# 03_CONNECTOR.net
KiCad netlist of a schematic drawn in Altium Designer
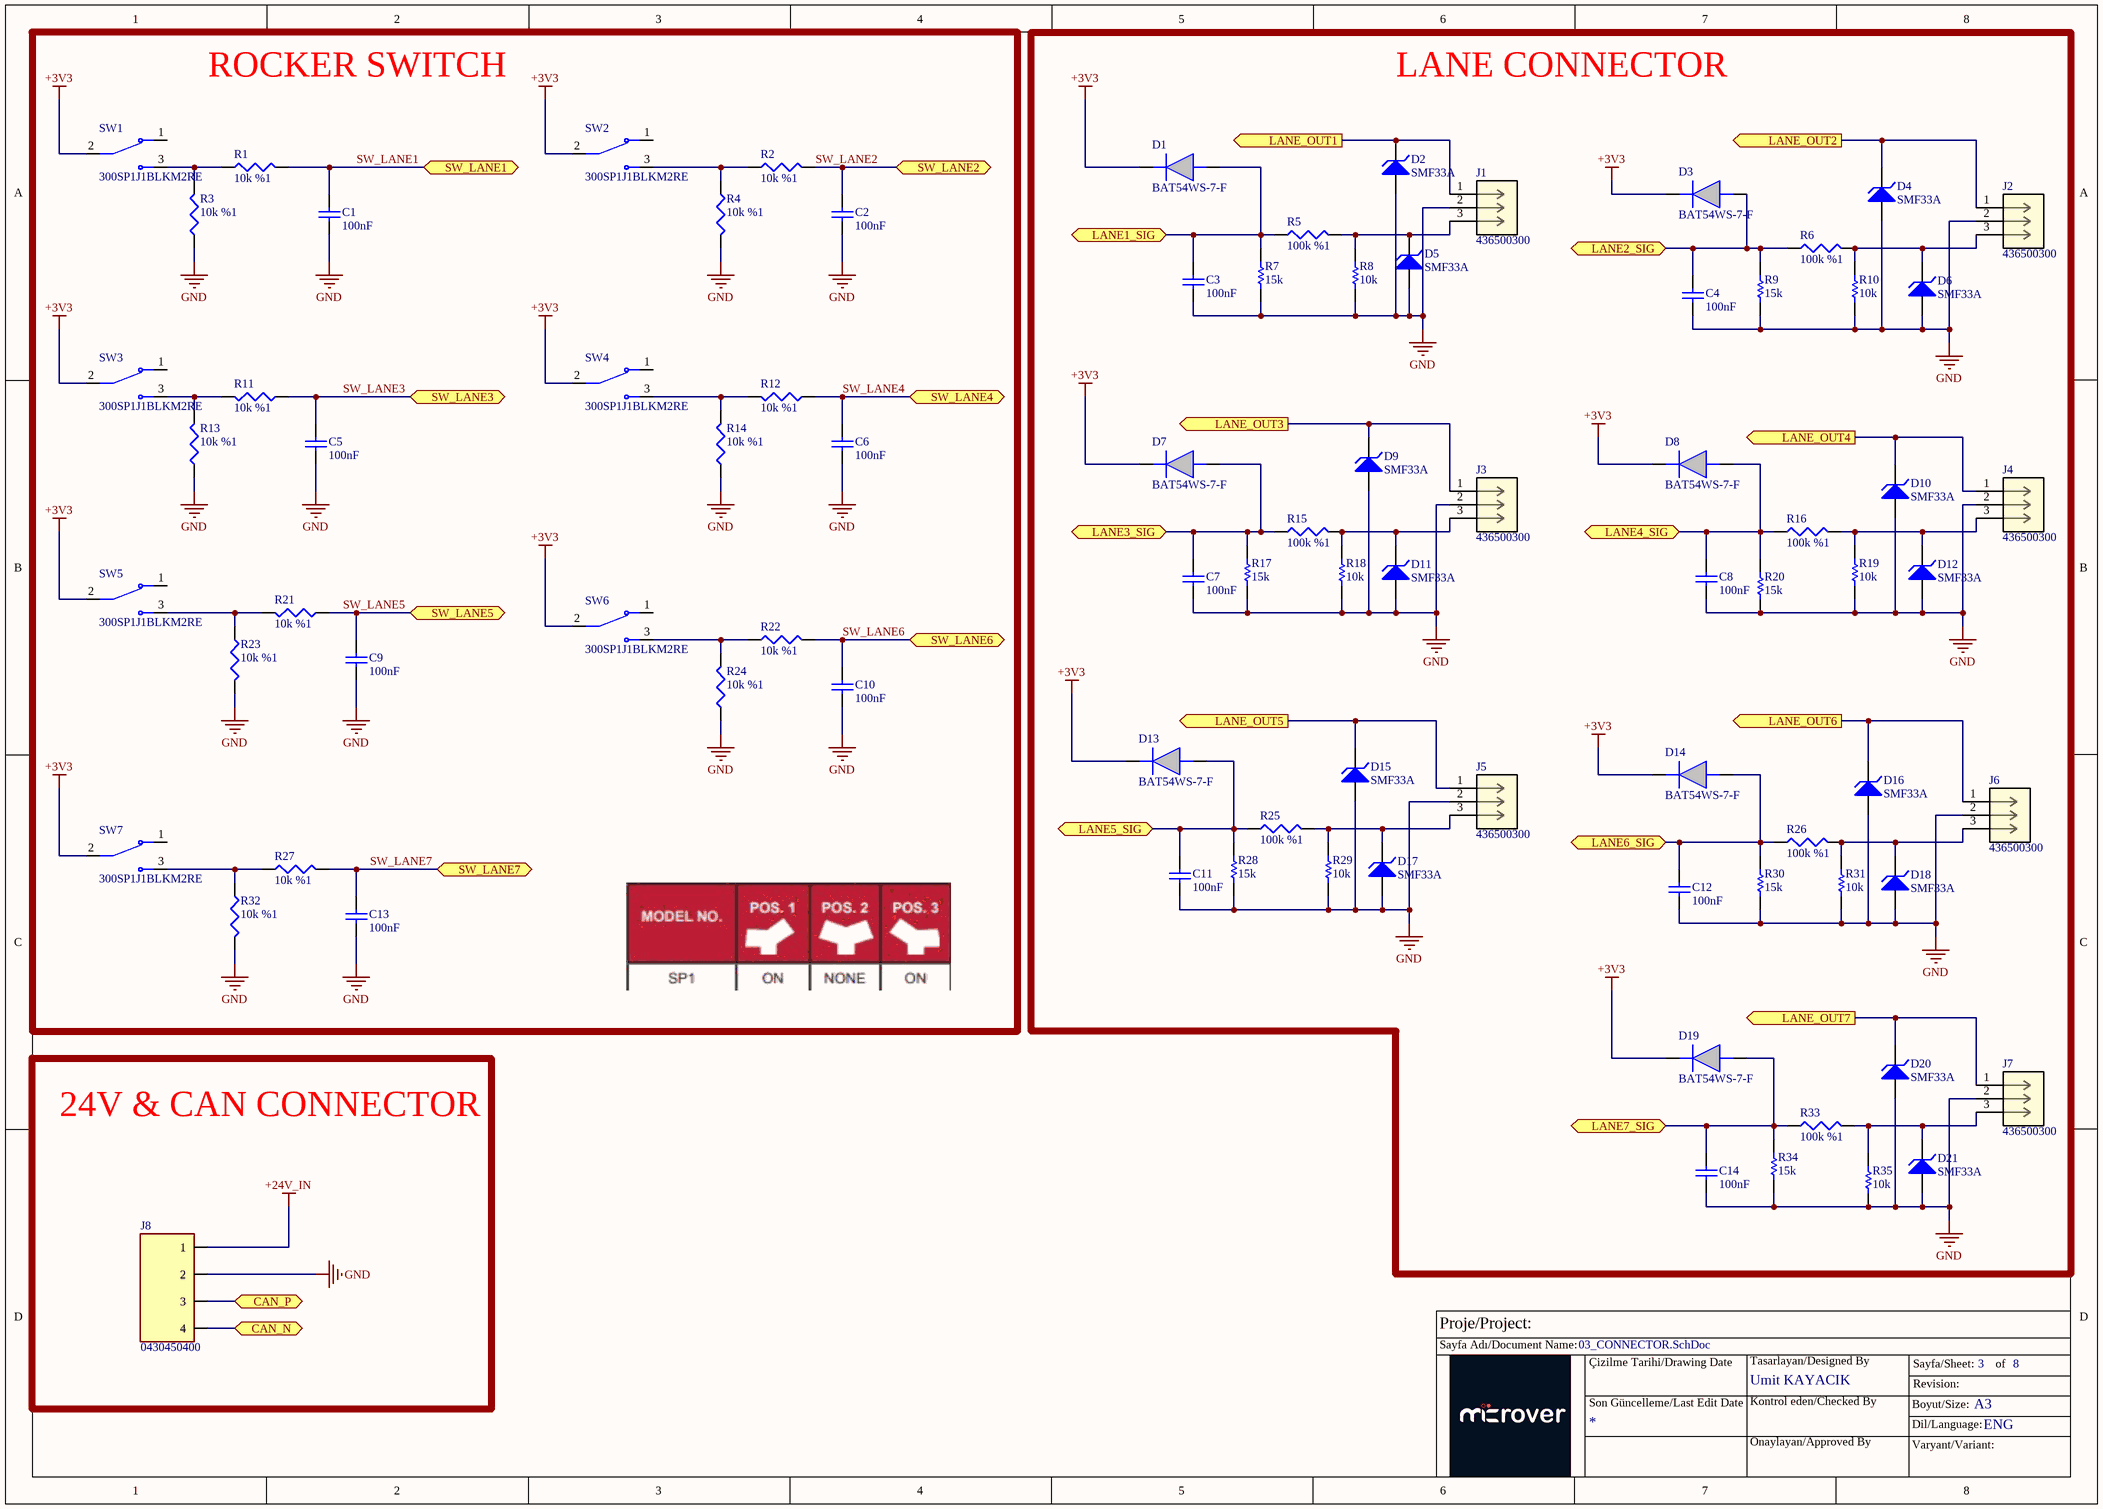
[diagram p0: 03_CONNECTOR.SchDoc]

(export (version "E")
  (design (tool "Eeschema 10.0.6"))
  (components
    (comp (ref "C1")
      (value "100nF")
      (footprint "CAP0603")
      (description "0.1 µF ±10% 50V Ceramic Capacitor X7R 0603 (1608 Metric)")
      (fields (field (name "MANUFACTURER PART NUMBER") "C0603C104K5RAC7867"))
      (libsource (lib "HW_ADHERENT_LANECTRL_R1") (part "CAP0603_100nF_50V"))
    )
    (comp (ref "C2")
      (value "100nF")
      (footprint "CAP0603")
      (description "0.1 µF ±10% 50V Ceramic Capacitor X7R 0603 (1608 Metric)")
      (fields (field (name "MANUFACTURER PART NUMBER") "C0603C104K5RAC7867"))
      (libsource (lib "HW_ADHERENT_LANECTRL_R1") (part "CAP0603_100nF_50V"))
    )
    (comp (ref "C3")
      (value "100nF")
      (footprint "CAP0603")
      (description "0.1 µF ±10% 50V Ceramic Capacitor X7R 0603 (1608 Metric)")
      (fields (field (name "MANUFACTURER PART NUMBER") "C0603C104K5RAC7867"))
      (libsource (lib "HW_ADHERENT_LANECTRL_R1") (part "CAP0603_100nF_50V"))
    )
    (comp (ref "C4")
      (value "100nF")
      (footprint "CAP0603")
      (description "0.1 µF ±10% 50V Ceramic Capacitor X7R 0603 (1608 Metric)")
      (fields (field (name "MANUFACTURER PART NUMBER") "C0603C104K5RAC7867"))
      (libsource (lib "HW_ADHERENT_LANECTRL_R1") (part "CAP0603_100nF_50V"))
    )
    (comp (ref "C5")
      (value "100nF")
      (footprint "CAP0603")
      (description "0.1 µF ±10% 50V Ceramic Capacitor X7R 0603 (1608 Metric)")
      (fields (field (name "MANUFACTURER PART NUMBER") "C0603C104K5RAC7867"))
      (libsource (lib "HW_ADHERENT_LANECTRL_R1") (part "CAP0603_100nF_50V"))
    )
    (comp (ref "C6")
      (value "100nF")
      (footprint "CAP0603")
      (description "0.1 µF ±10% 50V Ceramic Capacitor X7R 0603 (1608 Metric)")
      (fields (field (name "MANUFACTURER PART NUMBER") "C0603C104K5RAC7867"))
      (libsource (lib "HW_ADHERENT_LANECTRL_R1") (part "CAP0603_100nF_50V"))
    )
    (comp (ref "C7")
      (value "100nF")
      (footprint "CAP0603")
      (description "0.1 µF ±10% 50V Ceramic Capacitor X7R 0603 (1608 Metric)")
      (fields (field (name "MANUFACTURER PART NUMBER") "C0603C104K5RAC7867"))
      (libsource (lib "HW_ADHERENT_LANECTRL_R1") (part "CAP0603_100nF_50V"))
    )
    (comp (ref "C8")
      (value "100nF")
      (footprint "CAP0603")
      (description "0.1 µF ±10% 50V Ceramic Capacitor X7R 0603 (1608 Metric)")
      (fields (field (name "MANUFACTURER PART NUMBER") "C0603C104K5RAC7867"))
      (libsource (lib "HW_ADHERENT_LANECTRL_R1") (part "CAP0603_100nF_50V"))
    )
    (comp (ref "C9")
      (value "100nF")
      (footprint "CAP0603")
      (description "0.1 µF ±10% 50V Ceramic Capacitor X7R 0603 (1608 Metric)")
      (fields (field (name "MANUFACTURER PART NUMBER") "C0603C104K5RAC7867"))
      (libsource (lib "HW_ADHERENT_LANECTRL_R1") (part "CAP0603_100nF_50V"))
    )
    (comp (ref "C10")
      (value "100nF")
      (footprint "CAP0603")
      (description "0.1 µF ±10% 50V Ceramic Capacitor X7R 0603 (1608 Metric)")
      (fields (field (name "MANUFACTURER PART NUMBER") "C0603C104K5RAC7867"))
      (libsource (lib "HW_ADHERENT_LANECTRL_R1") (part "CAP0603_100nF_50V"))
    )
    (comp (ref "C11")
      (value "100nF")
      (footprint "CAP0603")
      (description "0.1 µF ±10% 50V Ceramic Capacitor X7R 0603 (1608 Metric)")
      (fields (field (name "MANUFACTURER PART NUMBER") "C0603C104K5RAC7867"))
      (libsource (lib "HW_ADHERENT_LANECTRL_R1") (part "CAP0603_100nF_50V"))
    )
    (comp (ref "C12")
      (value "100nF")
      (footprint "CAP0603")
      (description "0.1 µF ±10% 50V Ceramic Capacitor X7R 0603 (1608 Metric)")
      (fields (field (name "MANUFACTURER PART NUMBER") "C0603C104K5RAC7867"))
      (libsource (lib "HW_ADHERENT_LANECTRL_R1") (part "CAP0603_100nF_50V"))
    )
    (comp (ref "C13")
      (value "100nF")
      (footprint "CAP0603")
      (description "0.1 µF ±10% 50V Ceramic Capacitor X7R 0603 (1608 Metric)")
      (fields (field (name "MANUFACTURER PART NUMBER") "C0603C104K5RAC7867"))
      (libsource (lib "HW_ADHERENT_LANECTRL_R1") (part "CAP0603_100nF_50V"))
    )
    (comp (ref "C14")
      (value "100nF")
      (footprint "CAP0603")
      (description "0.1 µF ±10% 50V Ceramic Capacitor X7R 0603 (1608 Metric)")
      (fields (field (name "MANUFACTURER PART NUMBER") "C0603C104K5RAC7867"))
      (libsource (lib "HW_ADHERENT_LANECTRL_R1") (part "CAP0603_100nF_50V"))
    )
    (comp (ref "D1")
      (value "BAT54WS-7-F")
      (footprint "SOD2513X120N")
      (description "Diode 30 V 100mA Surface Mount SOD-323")
      (libsource (lib "HW_ADHERENT_LANECTRL_R1") (part "BAT54WS-7-F"))
    )
    (comp (ref "D2")
      (value "SMF33A")
      (footprint "SOD-123F - duplicate")
      (description "53.3V Clamp 3.8A Ipp Tvs Diode Surface Mount SOD-123F")
      (fields (field (name "MANUFACTURER") "Littelfuse Inc."))
      (libsource (lib "HW_ADHERENT_LANECTRL_R1") (part "SMF33A"))
    )
    (comp (ref "D3")
      (value "BAT54WS-7-F")
      (footprint "SOD2513X120N")
      (description "Diode 30 V 100mA Surface Mount SOD-323")
      (libsource (lib "HW_ADHERENT_LANECTRL_R1") (part "BAT54WS-7-F"))
    )
    (comp (ref "D4")
      (value "SMF33A")
      (footprint "SOD-123F - duplicate")
      (description "53.3V Clamp 3.8A Ipp Tvs Diode Surface Mount SOD-123F")
      (fields (field (name "MANUFACTURER") "Littelfuse Inc."))
      (libsource (lib "HW_ADHERENT_LANECTRL_R1") (part "SMF33A"))
    )
    (comp (ref "D5")
      (value "SMF33A")
      (footprint "SOD-123F - duplicate")
      (description "53.3V Clamp 3.8A Ipp Tvs Diode Surface Mount SOD-123F")
      (fields (field (name "MANUFACTURER") "Littelfuse Inc."))
      (libsource (lib "HW_ADHERENT_LANECTRL_R1") (part "SMF33A"))
    )
    (comp (ref "D6")
      (value "SMF33A")
      (footprint "SOD-123F - duplicate")
      (description "53.3V Clamp 3.8A Ipp Tvs Diode Surface Mount SOD-123F")
      (fields (field (name "MANUFACTURER") "Littelfuse Inc."))
      (libsource (lib "HW_ADHERENT_LANECTRL_R1") (part "SMF33A"))
    )
    (comp (ref "D7")
      (value "BAT54WS-7-F")
      (footprint "SOD2513X120N")
      (description "Diode 30 V 100mA Surface Mount SOD-323")
      (libsource (lib "HW_ADHERENT_LANECTRL_R1") (part "BAT54WS-7-F"))
    )
    (comp (ref "D8")
      (value "BAT54WS-7-F")
      (footprint "SOD2513X120N")
      (description "Diode 30 V 100mA Surface Mount SOD-323")
      (libsource (lib "HW_ADHERENT_LANECTRL_R1") (part "BAT54WS-7-F"))
    )
    (comp (ref "D9")
      (value "SMF33A")
      (footprint "SOD-123F - duplicate")
      (description "53.3V Clamp 3.8A Ipp Tvs Diode Surface Mount SOD-123F")
      (fields (field (name "MANUFACTURER") "Littelfuse Inc."))
      (libsource (lib "HW_ADHERENT_LANECTRL_R1") (part "SMF33A"))
    )
    (comp (ref "D10")
      (value "SMF33A")
      (footprint "SOD-123F - duplicate")
      (description "53.3V Clamp 3.8A Ipp Tvs Diode Surface Mount SOD-123F")
      (fields (field (name "MANUFACTURER") "Littelfuse Inc."))
      (libsource (lib "HW_ADHERENT_LANECTRL_R1") (part "SMF33A"))
    )
    (comp (ref "D11")
      (value "SMF33A")
      (footprint "SOD-123F - duplicate")
      (description "53.3V Clamp 3.8A Ipp Tvs Diode Surface Mount SOD-123F")
      (fields (field (name "MANUFACTURER") "Littelfuse Inc."))
      (libsource (lib "HW_ADHERENT_LANECTRL_R1") (part "SMF33A"))
    )
    (comp (ref "D12")
      (value "SMF33A")
      (footprint "SOD-123F - duplicate")
      (description "53.3V Clamp 3.8A Ipp Tvs Diode Surface Mount SOD-123F")
      (fields (field (name "MANUFACTURER") "Littelfuse Inc."))
      (libsource (lib "HW_ADHERENT_LANECTRL_R1") (part "SMF33A"))
    )
    (comp (ref "D13")
      (value "BAT54WS-7-F")
      (footprint "SOD2513X120N")
      (description "Diode 30 V 100mA Surface Mount SOD-323")
      (libsource (lib "HW_ADHERENT_LANECTRL_R1") (part "BAT54WS-7-F"))
    )
    (comp (ref "D14")
      (value "BAT54WS-7-F")
      (footprint "SOD2513X120N")
      (description "Diode 30 V 100mA Surface Mount SOD-323")
      (libsource (lib "HW_ADHERENT_LANECTRL_R1") (part "BAT54WS-7-F"))
    )
    (comp (ref "D15")
      (value "SMF33A")
      (footprint "SOD-123F - duplicate")
      (description "53.3V Clamp 3.8A Ipp Tvs Diode Surface Mount SOD-123F")
      (fields (field (name "MANUFACTURER") "Littelfuse Inc."))
      (libsource (lib "HW_ADHERENT_LANECTRL_R1") (part "SMF33A"))
    )
    (comp (ref "D16")
      (value "SMF33A")
      (footprint "SOD-123F - duplicate")
      (description "53.3V Clamp 3.8A Ipp Tvs Diode Surface Mount SOD-123F")
      (fields (field (name "MANUFACTURER") "Littelfuse Inc."))
      (libsource (lib "HW_ADHERENT_LANECTRL_R1") (part "SMF33A"))
    )
    (comp (ref "D17")
      (value "SMF33A")
      (footprint "SOD-123F - duplicate")
      (description "53.3V Clamp 3.8A Ipp Tvs Diode Surface Mount SOD-123F")
      (fields (field (name "MANUFACTURER") "Littelfuse Inc."))
      (libsource (lib "HW_ADHERENT_LANECTRL_R1") (part "SMF33A"))
    )
    (comp (ref "D18")
      (value "SMF33A")
      (footprint "SOD-123F - duplicate")
      (description "53.3V Clamp 3.8A Ipp Tvs Diode Surface Mount SOD-123F")
      (fields (field (name "MANUFACTURER") "Littelfuse Inc."))
      (libsource (lib "HW_ADHERENT_LANECTRL_R1") (part "SMF33A"))
    )
    (comp (ref "D19")
      (value "BAT54WS-7-F")
      (footprint "SOD2513X120N")
      (description "Diode 30 V 100mA Surface Mount SOD-323")
      (libsource (lib "HW_ADHERENT_LANECTRL_R1") (part "BAT54WS-7-F"))
    )
    (comp (ref "D20")
      (value "SMF33A")
      (footprint "SOD-123F - duplicate")
      (description "53.3V Clamp 3.8A Ipp Tvs Diode Surface Mount SOD-123F")
      (fields (field (name "MANUFACTURER") "Littelfuse Inc."))
      (libsource (lib "HW_ADHERENT_LANECTRL_R1") (part "SMF33A"))
    )
    (comp (ref "D21")
      (value "SMF33A")
      (footprint "SOD-123F - duplicate")
      (description "53.3V Clamp 3.8A Ipp Tvs Diode Surface Mount SOD-123F")
      (fields (field (name "MANUFACTURER") "Littelfuse Inc."))
      (libsource (lib "HW_ADHERENT_LANECTRL_R1") (part "SMF33A"))
    )
    (comp (ref "J1")
      (value "436500300")
      (footprint "CONN_SD-43650-001_03_MOL/")
      (libsource (lib "HW_ADHERENT_LANECTRL_R1") (part "436500300"))
    )
    (comp (ref "J2")
      (value "436500300")
      (footprint "CONN_SD-43650-001_03_MOL/")
      (libsource (lib "HW_ADHERENT_LANECTRL_R1") (part "436500300"))
    )
    (comp (ref "J3")
      (value "436500300")
      (footprint "CONN_SD-43650-001_03_MOL/")
      (libsource (lib "HW_ADHERENT_LANECTRL_R1") (part "436500300"))
    )
    (comp (ref "J4")
      (value "436500300")
      (footprint "CONN_SD-43650-001_03_MOL/")
      (libsource (lib "HW_ADHERENT_LANECTRL_R1") (part "436500300"))
    )
    (comp (ref "J5")
      (value "436500300")
      (footprint "CONN_SD-43650-001_03_MOL/")
      (libsource (lib "HW_ADHERENT_LANECTRL_R1") (part "436500300"))
    )
    (comp (ref "J6")
      (value "436500300")
      (footprint "CONN_SD-43650-001_03_MOL/")
      (libsource (lib "HW_ADHERENT_LANECTRL_R1") (part "436500300"))
    )
    (comp (ref "J7")
      (value "436500300")
      (footprint "CONN_SD-43650-001_03_MOL/")
      (libsource (lib "HW_ADHERENT_LANECTRL_R1") (part "436500300"))
    )
    (comp (ref "J8")
      (value "0430450400")
      (footprint "CONN_SD-43045-001_04_MOL")
      (description "Connector Header Through Hole, Right Angle 4 position 0.118\" (3.00mm)")
      (fields (field (name "MANUFACTURER") "MOLEX"))
      (libsource (lib "HW_ADHERENT_LANECTRL_R1") (part "0430450400"))
    )
    (comp (ref "R1")
      (value "10k %1")
      (footprint "RESIS_0603")
      (description "Thick Film Resistors - SMD 0603 100 mW (1/10 W) 1% 10K")
      (fields (field (name "MANUFACTURER") "UNI-ROYAL(Uniroyal Elec)"))
      (libsource (lib "HW_ADHERENT_LANECTRL_R1") (part "0603WAF1002T5E"))
    )
    (comp (ref "R2")
      (value "10k %1")
      (footprint "RESIS_0603")
      (description "Thick Film Resistors - SMD 0603 100 mW (1/10 W) 1% 10K")
      (fields (field (name "MANUFACTURER") "UNI-ROYAL(Uniroyal Elec)"))
      (libsource (lib "HW_ADHERENT_LANECTRL_R1") (part "0603WAF1002T5E"))
    )
    (comp (ref "R3")
      (value "10k %1")
      (footprint "RESIS_0603")
      (description "Thick Film Resistors - SMD 0603 100 mW (1/10 W) 1% 10K")
      (fields (field (name "MANUFACTURER") "UNI-ROYAL(Uniroyal Elec)"))
      (libsource (lib "HW_ADHERENT_LANECTRL_R1") (part "0603WAF1002T5E"))
    )
    (comp (ref "R4")
      (value "10k %1")
      (footprint "RESIS_0603")
      (description "Thick Film Resistors - SMD 0603 100 mW (1/10 W) 1% 10K")
      (fields (field (name "MANUFACTURER") "UNI-ROYAL(Uniroyal Elec)"))
      (libsource (lib "HW_ADHERENT_LANECTRL_R1") (part "0603WAF1002T5E"))
    )
    (comp (ref "R5")
      (value "100k %1")
      (footprint "RESIS_0603")
      (fields (field (name "MANUFACTURER") "UNI-ROYAL(Uniroyal Elec)"))
      (libsource (lib "HW_ADHERENT_LANECTRL_R1") (part "0603WAF1003T5E"))
    )
    (comp (ref "R6")
      (value "100k %1")
      (footprint "RESIS_0603")
      (fields (field (name "MANUFACTURER") "UNI-ROYAL(Uniroyal Elec)"))
      (libsource (lib "HW_ADHERENT_LANECTRL_R1") (part "0603WAF1003T5E"))
    )
    (comp (ref "R7")
      (value "15k")
      (footprint "RESIS_0603")
      (fields
        (field (name "MANUFACTURER") "UNI-ROYAL(Uniroyal Elec)")
        (field (name "MOUSER PART NUMBER") "303-0603WAF1502T5E")
      )
      (libsource (lib "HW_ADHERENT_LANECTRL_R1") (part "0603WAF1502T5E"))
    )
    (comp (ref "R8")
      (value "10k")
      (footprint "RES0805")
      (fields (field (name "JLCPCB PART#") "C17414") (field (name "MANUFACTURER") "UNI-ROYAL(Uniroyal Elec)"))
      (libsource (lib "HW_ADHERENT_LANECTRL_R1") (part "0805W8F1002T5E"))
    )
    (comp (ref "R9")
      (value "15k")
      (footprint "RESIS_0603")
      (fields
        (field (name "MANUFACTURER") "UNI-ROYAL(Uniroyal Elec)")
        (field (name "MOUSER PART NUMBER") "303-0603WAF1502T5E")
      )
      (libsource (lib "HW_ADHERENT_LANECTRL_R1") (part "0603WAF1502T5E"))
    )
    (comp (ref "R10")
      (value "10k")
      (footprint "RES0805")
      (fields (field (name "JLCPCB PART#") "C17414") (field (name "MANUFACTURER") "UNI-ROYAL(Uniroyal Elec)"))
      (libsource (lib "HW_ADHERENT_LANECTRL_R1") (part "0805W8F1002T5E"))
    )
    (comp (ref "R11")
      (value "10k %1")
      (footprint "RESIS_0603")
      (description "Thick Film Resistors - SMD 0603 100 mW (1/10 W) 1% 10K")
      (fields (field (name "MANUFACTURER") "UNI-ROYAL(Uniroyal Elec)"))
      (libsource (lib "HW_ADHERENT_LANECTRL_R1") (part "0603WAF1002T5E"))
    )
    (comp (ref "R12")
      (value "10k %1")
      (footprint "RESIS_0603")
      (description "Thick Film Resistors - SMD 0603 100 mW (1/10 W) 1% 10K")
      (fields (field (name "MANUFACTURER") "UNI-ROYAL(Uniroyal Elec)"))
      (libsource (lib "HW_ADHERENT_LANECTRL_R1") (part "0603WAF1002T5E"))
    )
    (comp (ref "R13")
      (value "10k %1")
      (footprint "RESIS_0603")
      (description "Thick Film Resistors - SMD 0603 100 mW (1/10 W) 1% 10K")
      (fields (field (name "MANUFACTURER") "UNI-ROYAL(Uniroyal Elec)"))
      (libsource (lib "HW_ADHERENT_LANECTRL_R1") (part "0603WAF1002T5E"))
    )
    (comp (ref "R14")
      (value "10k %1")
      (footprint "RESIS_0603")
      (description "Thick Film Resistors - SMD 0603 100 mW (1/10 W) 1% 10K")
      (fields (field (name "MANUFACTURER") "UNI-ROYAL(Uniroyal Elec)"))
      (libsource (lib "HW_ADHERENT_LANECTRL_R1") (part "0603WAF1002T5E"))
    )
    (comp (ref "R15")
      (value "100k %1")
      (footprint "RESIS_0603")
      (fields (field (name "MANUFACTURER") "UNI-ROYAL(Uniroyal Elec)"))
      (libsource (lib "HW_ADHERENT_LANECTRL_R1") (part "0603WAF1003T5E"))
    )
    (comp (ref "R16")
      (value "100k %1")
      (footprint "RESIS_0603")
      (fields (field (name "MANUFACTURER") "UNI-ROYAL(Uniroyal Elec)"))
      (libsource (lib "HW_ADHERENT_LANECTRL_R1") (part "0603WAF1003T5E"))
    )
    (comp (ref "R17")
      (value "15k")
      (footprint "RESIS_0603")
      (fields
        (field (name "MANUFACTURER") "UNI-ROYAL(Uniroyal Elec)")
        (field (name "MOUSER PART NUMBER") "303-0603WAF1502T5E")
      )
      (libsource (lib "HW_ADHERENT_LANECTRL_R1") (part "0603WAF1502T5E"))
    )
    (comp (ref "R18")
      (value "10k")
      (footprint "RES0805")
      (fields (field (name "JLCPCB PART#") "C17414") (field (name "MANUFACTURER") "UNI-ROYAL(Uniroyal Elec)"))
      (libsource (lib "HW_ADHERENT_LANECTRL_R1") (part "0805W8F1002T5E"))
    )
    (comp (ref "R19")
      (value "10k")
      (footprint "RES0805")
      (fields (field (name "JLCPCB PART#") "C17414") (field (name "MANUFACTURER") "UNI-ROYAL(Uniroyal Elec)"))
      (libsource (lib "HW_ADHERENT_LANECTRL_R1") (part "0805W8F1002T5E"))
    )
    (comp (ref "R20")
      (value "15k")
      (footprint "RESIS_0603")
      (fields
        (field (name "MANUFACTURER") "UNI-ROYAL(Uniroyal Elec)")
        (field (name "MOUSER PART NUMBER") "303-0603WAF1502T5E")
      )
      (libsource (lib "HW_ADHERENT_LANECTRL_R1") (part "0603WAF1502T5E"))
    )
    (comp (ref "R21")
      (value "10k %1")
      (footprint "RESIS_0603")
      (description "Thick Film Resistors - SMD 0603 100 mW (1/10 W) 1% 10K")
      (fields (field (name "MANUFACTURER") "UNI-ROYAL(Uniroyal Elec)"))
      (libsource (lib "HW_ADHERENT_LANECTRL_R1") (part "0603WAF1002T5E"))
    )
    (comp (ref "R22")
      (value "10k %1")
      (footprint "RESIS_0603")
      (description "Thick Film Resistors - SMD 0603 100 mW (1/10 W) 1% 10K")
      (fields (field (name "MANUFACTURER") "UNI-ROYAL(Uniroyal Elec)"))
      (libsource (lib "HW_ADHERENT_LANECTRL_R1") (part "0603WAF1002T5E"))
    )
    (comp (ref "R23")
      (value "10k %1")
      (footprint "RESIS_0603")
      (description "Thick Film Resistors - SMD 0603 100 mW (1/10 W) 1% 10K")
      (fields (field (name "MANUFACTURER") "UNI-ROYAL(Uniroyal Elec)"))
      (libsource (lib "HW_ADHERENT_LANECTRL_R1") (part "0603WAF1002T5E"))
    )
    (comp (ref "R24")
      (value "10k %1")
      (footprint "RESIS_0603")
      (description "Thick Film Resistors - SMD 0603 100 mW (1/10 W) 1% 10K")
      (fields (field (name "MANUFACTURER") "UNI-ROYAL(Uniroyal Elec)"))
      (libsource (lib "HW_ADHERENT_LANECTRL_R1") (part "0603WAF1002T5E"))
    )
    (comp (ref "R25")
      (value "100k %1")
      (footprint "RESIS_0603")
      (fields (field (name "MANUFACTURER") "UNI-ROYAL(Uniroyal Elec)"))
      (libsource (lib "HW_ADHERENT_LANECTRL_R1") (part "0603WAF1003T5E"))
    )
    (comp (ref "R26")
      (value "100k %1")
      (footprint "RESIS_0603")
      (fields (field (name "MANUFACTURER") "UNI-ROYAL(Uniroyal Elec)"))
      (libsource (lib "HW_ADHERENT_LANECTRL_R1") (part "0603WAF1003T5E"))
    )
    (comp (ref "R27")
      (value "10k %1")
      (footprint "RESIS_0603")
      (description "Thick Film Resistors - SMD 0603 100 mW (1/10 W) 1% 10K")
      (fields (field (name "MANUFACTURER") "UNI-ROYAL(Uniroyal Elec)"))
      (libsource (lib "HW_ADHERENT_LANECTRL_R1") (part "0603WAF1002T5E"))
    )
    (comp (ref "R28")
      (value "15k")
      (footprint "RESIS_0603")
      (fields
        (field (name "MANUFACTURER") "UNI-ROYAL(Uniroyal Elec)")
        (field (name "MOUSER PART NUMBER") "303-0603WAF1502T5E")
      )
      (libsource (lib "HW_ADHERENT_LANECTRL_R1") (part "0603WAF1502T5E"))
    )
    (comp (ref "R29")
      (value "10k")
      (footprint "RES0805")
      (fields (field (name "JLCPCB PART#") "C17414") (field (name "MANUFACTURER") "UNI-ROYAL(Uniroyal Elec)"))
      (libsource (lib "HW_ADHERENT_LANECTRL_R1") (part "0805W8F1002T5E"))
    )
    (comp (ref "R30")
      (value "15k")
      (footprint "RESIS_0603")
      (fields
        (field (name "MANUFACTURER") "UNI-ROYAL(Uniroyal Elec)")
        (field (name "MOUSER PART NUMBER") "303-0603WAF1502T5E")
      )
      (libsource (lib "HW_ADHERENT_LANECTRL_R1") (part "0603WAF1502T5E"))
    )
    (comp (ref "R31")
      (value "10k")
      (footprint "RES0805")
      (fields (field (name "JLCPCB PART#") "C17414") (field (name "MANUFACTURER") "UNI-ROYAL(Uniroyal Elec)"))
      (libsource (lib "HW_ADHERENT_LANECTRL_R1") (part "0805W8F1002T5E"))
    )
    (comp (ref "R32")
      (value "10k %1")
      (footprint "RESIS_0603")
      (description "Thick Film Resistors - SMD 0603 100 mW (1/10 W) 1% 10K")
      (fields (field (name "MANUFACTURER") "UNI-ROYAL(Uniroyal Elec)"))
      (libsource (lib "HW_ADHERENT_LANECTRL_R1") (part "0603WAF1002T5E"))
    )
    (comp (ref "R33")
      (value "100k %1")
      (footprint "RESIS_0603")
      (fields (field (name "MANUFACTURER") "UNI-ROYAL(Uniroyal Elec)"))
      (libsource (lib "HW_ADHERENT_LANECTRL_R1") (part "0603WAF1003T5E"))
    )
    (comp (ref "R34")
      (value "15k")
      (footprint "RESIS_0603")
      (fields
        (field (name "MANUFACTURER") "UNI-ROYAL(Uniroyal Elec)")
        (field (name "MOUSER PART NUMBER") "303-0603WAF1502T5E")
      )
      (libsource (lib "HW_ADHERENT_LANECTRL_R1") (part "0603WAF1502T5E"))
    )
    (comp (ref "R35")
      (value "10k")
      (footprint "RES0805")
      (fields (field (name "JLCPCB PART#") "C17414") (field (name "MANUFACTURER") "UNI-ROYAL(Uniroyal Elec)"))
      (libsource (lib "HW_ADHERENT_LANECTRL_R1") (part "0805W8F1002T5E"))
    )
    (comp (ref "SW1")
      (value "300SP1J1BLKM2RE")
      (footprint "sw_300SP1J1BLKM2RE_")
      (description "Rocker Switch SPDT 0.4VA (AC/DC) 20 V Through Hole")
      (fields (field (name "MANUFACTURER") "E-Switch"))
      (libsource (lib "HW_ADHERENT_LANECTRL_R1") (part "300SP1J1BLKM2RE"))
    )
    (comp (ref "SW2")
      (value "300SP1J1BLKM2RE")
      (footprint "sw_300SP1J1BLKM2RE_")
      (description "Rocker Switch SPDT 0.4VA (AC/DC) 20 V Through Hole")
      (fields (field (name "MANUFACTURER") "E-Switch"))
      (libsource (lib "HW_ADHERENT_LANECTRL_R1") (part "300SP1J1BLKM2RE"))
    )
    (comp (ref "SW3")
      (value "300SP1J1BLKM2RE")
      (footprint "sw_300SP1J1BLKM2RE_")
      (description "Rocker Switch SPDT 0.4VA (AC/DC) 20 V Through Hole")
      (fields (field (name "MANUFACTURER") "E-Switch"))
      (libsource (lib "HW_ADHERENT_LANECTRL_R1") (part "300SP1J1BLKM2RE"))
    )
    (comp (ref "SW4")
      (value "300SP1J1BLKM2RE")
      (footprint "sw_300SP1J1BLKM2RE_")
      (description "Rocker Switch SPDT 0.4VA (AC/DC) 20 V Through Hole")
      (fields (field (name "MANUFACTURER") "E-Switch"))
      (libsource (lib "HW_ADHERENT_LANECTRL_R1") (part "300SP1J1BLKM2RE"))
    )
    (comp (ref "SW5")
      (value "300SP1J1BLKM2RE")
      (footprint "sw_300SP1J1BLKM2RE_")
      (description "Rocker Switch SPDT 0.4VA (AC/DC) 20 V Through Hole")
      (fields (field (name "MANUFACTURER") "E-Switch"))
      (libsource (lib "HW_ADHERENT_LANECTRL_R1") (part "300SP1J1BLKM2RE"))
    )
    (comp (ref "SW6")
      (value "300SP1J1BLKM2RE")
      (footprint "sw_300SP1J1BLKM2RE_")
      (description "Rocker Switch SPDT 0.4VA (AC/DC) 20 V Through Hole")
      (fields (field (name "MANUFACTURER") "E-Switch"))
      (libsource (lib "HW_ADHERENT_LANECTRL_R1") (part "300SP1J1BLKM2RE"))
    )
    (comp (ref "SW7")
      (value "300SP1J1BLKM2RE")
      (footprint "sw_300SP1J1BLKM2RE_")
      (description "Rocker Switch SPDT 0.4VA (AC/DC) 20 V Through Hole")
      (fields (field (name "MANUFACTURER") "E-Switch"))
      (libsource (lib "HW_ADHERENT_LANECTRL_R1") (part "300SP1J1BLKM2RE"))
    )
  )
  (nets
    (net (code "1") (name "+3V3") (class "Default")
      (node (ref "D1") (pin "1") (pinfunction "K_1") (pintype "passive"))
      (node (ref "D13") (pin "1") (pinfunction "K_1") (pintype "passive"))
      (node (ref "D14") (pin "1") (pinfunction "K_1") (pintype "passive"))
      (node (ref "D19") (pin "1") (pinfunction "K_1") (pintype "passive"))
      (node (ref "D3") (pin "1") (pinfunction "K_1") (pintype "passive"))
      (node (ref "D7") (pin "1") (pinfunction "K_1") (pintype "passive"))
      (node (ref "D8") (pin "1") (pinfunction "K_1") (pintype "passive"))
      (node (ref "SW1") (pin "2") (pinfunction "2_2") (pintype "passive"))
      (node (ref "SW2") (pin "2") (pinfunction "2_2") (pintype "passive"))
      (node (ref "SW3") (pin "2") (pinfunction "2_2") (pintype "passive"))
      (node (ref "SW4") (pin "2") (pinfunction "2_2") (pintype "passive"))
      (node (ref "SW5") (pin "2") (pinfunction "2_2") (pintype "passive"))
      (node (ref "SW6") (pin "2") (pinfunction "2_2") (pintype "passive"))
      (node (ref "SW7") (pin "2") (pinfunction "2_2") (pintype "passive"))
    )
    (net (code "2") (name "+24V_IN") (class "Default")
      (node (ref "J8") (pin "1") (pinfunction "1_1") (pintype "passive"))
    )
    (net (code "3") (name "/CAN_N") (class "Default")
      (node (ref "J8") (pin "4") (pinfunction "4_4") (pintype "passive"))
    )
    (net (code "4") (name "/CAN_P") (class "Default")
      (node (ref "J8") (pin "3") (pinfunction "3_3") (pintype "passive"))
    )
    (net (code "5") (name "/LANE1_SIG") (class "Default")
      (node (ref "C3") (pin "2") (pinfunction "2_2") (pintype "passive"))
      (node (ref "D1") (pin "2") (pinfunction "A_2") (pintype "passive"))
      (node (ref "R5") (pin "1") (pinfunction "1_1") (pintype "passive"))
      (node (ref "R7") (pin "2") (pinfunction "2_2") (pintype "passive"))
    )
    (net (code "6") (name "/LANE2_SIG") (class "Default")
      (node (ref "C4") (pin "2") (pinfunction "2_2") (pintype "passive"))
      (node (ref "D3") (pin "2") (pinfunction "A_2") (pintype "passive"))
      (node (ref "R6") (pin "1") (pinfunction "1_1") (pintype "passive"))
      (node (ref "R9") (pin "2") (pinfunction "2_2") (pintype "passive"))
    )
    (net (code "7") (name "/LANE3_SIG") (class "Default")
      (node (ref "C7") (pin "2") (pinfunction "2_2") (pintype "passive"))
      (node (ref "D7") (pin "2") (pinfunction "A_2") (pintype "passive"))
      (node (ref "R15") (pin "1") (pinfunction "1_1") (pintype "passive"))
      (node (ref "R17") (pin "2") (pinfunction "2_2") (pintype "passive"))
    )
    (net (code "8") (name "/LANE4_SIG") (class "Default")
      (node (ref "C8") (pin "2") (pinfunction "2_2") (pintype "passive"))
      (node (ref "D8") (pin "2") (pinfunction "A_2") (pintype "passive"))
      (node (ref "R16") (pin "1") (pinfunction "1_1") (pintype "passive"))
      (node (ref "R20") (pin "2") (pinfunction "2_2") (pintype "passive"))
    )
    (net (code "9") (name "/LANE5_SIG") (class "Default")
      (node (ref "C11") (pin "2") (pinfunction "2_2") (pintype "passive"))
      (node (ref "D13") (pin "2") (pinfunction "A_2") (pintype "passive"))
      (node (ref "R25") (pin "1") (pinfunction "1_1") (pintype "passive"))
      (node (ref "R28") (pin "2") (pinfunction "2_2") (pintype "passive"))
    )
    (net (code "10") (name "/LANE6_SIG") (class "Default")
      (node (ref "C12") (pin "2") (pinfunction "2_2") (pintype "passive"))
      (node (ref "D14") (pin "2") (pinfunction "A_2") (pintype "passive"))
      (node (ref "R26") (pin "1") (pinfunction "1_1") (pintype "passive"))
      (node (ref "R30") (pin "2") (pinfunction "2_2") (pintype "passive"))
    )
    (net (code "11") (name "/LANE7_SIG") (class "Default")
      (node (ref "C14") (pin "2") (pinfunction "2_2") (pintype "passive"))
      (node (ref "D19") (pin "2") (pinfunction "A_2") (pintype "passive"))
      (node (ref "R33") (pin "1") (pinfunction "1_1") (pintype "passive"))
      (node (ref "R34") (pin "2") (pinfunction "2_2") (pintype "passive"))
    )
    (net (code "12") (name "/LANE_OUT1") (class "Default")
      (node (ref "D2") (pin "1") (pinfunction "K_1") (pintype "passive"))
      (node (ref "J1") (pin "1") (pinfunction "1_1") (pintype "passive"))
    )
    (net (code "13") (name "/LANE_OUT2") (class "Default")
      (node (ref "D4") (pin "1") (pinfunction "K_1") (pintype "passive"))
      (node (ref "J2") (pin "1") (pinfunction "1_1") (pintype "passive"))
    )
    (net (code "14") (name "/LANE_OUT3") (class "Default")
      (node (ref "D9") (pin "1") (pinfunction "K_1") (pintype "passive"))
      (node (ref "J3") (pin "1") (pinfunction "1_1") (pintype "passive"))
    )
    (net (code "15") (name "/LANE_OUT4") (class "Default")
      (node (ref "D10") (pin "1") (pinfunction "K_1") (pintype "passive"))
      (node (ref "J4") (pin "1") (pinfunction "1_1") (pintype "passive"))
    )
    (net (code "16") (name "/LANE_OUT5") (class "Default")
      (node (ref "D15") (pin "1") (pinfunction "K_1") (pintype "passive"))
      (node (ref "J5") (pin "1") (pinfunction "1_1") (pintype "passive"))
    )
    (net (code "17") (name "/LANE_OUT6") (class "Default")
      (node (ref "D16") (pin "1") (pinfunction "K_1") (pintype "passive"))
      (node (ref "J6") (pin "1") (pinfunction "1_1") (pintype "passive"))
    )
    (net (code "18") (name "/LANE_OUT7") (class "Default")
      (node (ref "D20") (pin "1") (pinfunction "K_1") (pintype "passive"))
      (node (ref "J7") (pin "1") (pinfunction "1_1") (pintype "passive"))
    )
    (net (code "19") (name "/SW_LANE1") (class "Default")
      (node (ref "C1") (pin "2") (pinfunction "2_2") (pintype "passive"))
      (node (ref "R1") (pin "2") (pinfunction "2_2") (pintype "passive"))
    )
    (net (code "20") (name "/SW_LANE2") (class "Default")
      (node (ref "C2") (pin "2") (pinfunction "2_2") (pintype "passive"))
      (node (ref "R2") (pin "2") (pinfunction "2_2") (pintype "passive"))
    )
    (net (code "21") (name "/SW_LANE3") (class "Default")
      (node (ref "C5") (pin "2") (pinfunction "2_2") (pintype "passive"))
      (node (ref "R11") (pin "1") (pinfunction "1_1") (pintype "passive"))
    )
    (net (code "22") (name "/SW_LANE4") (class "Default")
      (node (ref "C6") (pin "2") (pinfunction "2_2") (pintype "passive"))
      (node (ref "R12") (pin "1") (pinfunction "1_1") (pintype "passive"))
    )
    (net (code "23") (name "/SW_LANE5") (class "Default")
      (node (ref "C9") (pin "2") (pinfunction "2_2") (pintype "passive"))
      (node (ref "R21") (pin "1") (pinfunction "1_1") (pintype "passive"))
    )
    (net (code "24") (name "/SW_LANE6") (class "Default")
      (node (ref "C10") (pin "2") (pinfunction "2_2") (pintype "passive"))
      (node (ref "R22") (pin "2") (pinfunction "2_2") (pintype "passive"))
    )
    (net (code "25") (name "/SW_LANE7") (class "Default")
      (node (ref "C13") (pin "2") (pinfunction "2_2") (pintype "passive"))
      (node (ref "R27") (pin "2") (pinfunction "2_2") (pintype "passive"))
    )
    (net (code "26") (name "GND") (class "Default")
      (node (ref "C1") (pin "1") (pinfunction "1_1") (pintype "passive"))
      (node (ref "C10") (pin "1") (pinfunction "1_1") (pintype "passive"))
      (node (ref "C11") (pin "1") (pinfunction "1_1") (pintype "passive"))
      (node (ref "C12") (pin "1") (pinfunction "1_1") (pintype "passive"))
      (node (ref "C13") (pin "1") (pinfunction "1_1") (pintype "passive"))
      (node (ref "C14") (pin "1") (pinfunction "1_1") (pintype "passive"))
      (node (ref "C2") (pin "1") (pinfunction "1_1") (pintype "passive"))
      (node (ref "C3") (pin "1") (pinfunction "1_1") (pintype "passive"))
      (node (ref "C4") (pin "1") (pinfunction "1_1") (pintype "passive"))
      (node (ref "C5") (pin "1") (pinfunction "1_1") (pintype "passive"))
      (node (ref "C6") (pin "1") (pinfunction "1_1") (pintype "passive"))
      (node (ref "C7") (pin "1") (pinfunction "1_1") (pintype "passive"))
      (node (ref "C8") (pin "1") (pinfunction "1_1") (pintype "passive"))
      (node (ref "C9") (pin "1") (pinfunction "1_1") (pintype "passive"))
      (node (ref "D10") (pin "2") (pinfunction "A_2") (pintype "passive"))
      (node (ref "D11") (pin "2") (pinfunction "A_2") (pintype "passive"))
      (node (ref "D12") (pin "2") (pinfunction "A_2") (pintype "passive"))
      (node (ref "D15") (pin "2") (pinfunction "A_2") (pintype "passive"))
      (node (ref "D16") (pin "2") (pinfunction "A_2") (pintype "passive"))
      (node (ref "D17") (pin "2") (pinfunction "A_2") (pintype "passive"))
      (node (ref "D18") (pin "2") (pinfunction "A_2") (pintype "passive"))
      (node (ref "D2") (pin "2") (pinfunction "A_2") (pintype "passive"))
      (node (ref "D20") (pin "2") (pinfunction "A_2") (pintype "passive"))
      (node (ref "D21") (pin "2") (pinfunction "A_2") (pintype "passive"))
      (node (ref "D4") (pin "2") (pinfunction "A_2") (pintype "passive"))
      (node (ref "D5") (pin "2") (pinfunction "A_2") (pintype "passive"))
      (node (ref "D6") (pin "2") (pinfunction "A_2") (pintype "passive"))
      (node (ref "D9") (pin "2") (pinfunction "A_2") (pintype "passive"))
      (node (ref "J1") (pin "2") (pinfunction "2_2") (pintype "passive"))
      (node (ref "J2") (pin "2") (pinfunction "2_2") (pintype "passive"))
      (node (ref "J3") (pin "2") (pinfunction "2_2") (pintype "passive"))
      (node (ref "J4") (pin "2") (pinfunction "2_2") (pintype "passive"))
      (node (ref "J5") (pin "2") (pinfunction "2_2") (pintype "passive"))
      (node (ref "J6") (pin "2") (pinfunction "2_2") (pintype "passive"))
      (node (ref "J7") (pin "2") (pinfunction "2_2") (pintype "passive"))
      (node (ref "J8") (pin "2") (pinfunction "2_2") (pintype "passive"))
      (node (ref "R10") (pin "1") (pinfunction "1_1") (pintype "passive"))
      (node (ref "R13") (pin "1") (pinfunction "1_1") (pintype "passive"))
      (node (ref "R14") (pin "1") (pinfunction "1_1") (pintype "passive"))
      (node (ref "R17") (pin "1") (pinfunction "1_1") (pintype "passive"))
      (node (ref "R18") (pin "1") (pinfunction "1_1") (pintype "passive"))
      (node (ref "R19") (pin "1") (pinfunction "1_1") (pintype "passive"))
      (node (ref "R20") (pin "1") (pinfunction "1_1") (pintype "passive"))
      (node (ref "R23") (pin "2") (pinfunction "2_2") (pintype "passive"))
      (node (ref "R24") (pin "1") (pinfunction "1_1") (pintype "passive"))
      (node (ref "R28") (pin "1") (pinfunction "1_1") (pintype "passive"))
      (node (ref "R29") (pin "1") (pinfunction "1_1") (pintype "passive"))
      (node (ref "R3") (pin "1") (pinfunction "1_1") (pintype "passive"))
      (node (ref "R30") (pin "1") (pinfunction "1_1") (pintype "passive"))
      (node (ref "R31") (pin "1") (pinfunction "1_1") (pintype "passive"))
      (node (ref "R32") (pin "2") (pinfunction "2_2") (pintype "passive"))
      (node (ref "R34") (pin "1") (pinfunction "1_1") (pintype "passive"))
      (node (ref "R35") (pin "1") (pinfunction "1_1") (pintype "passive"))
      (node (ref "R4") (pin "2") (pinfunction "2_2") (pintype "passive"))
      (node (ref "R7") (pin "1") (pinfunction "1_1") (pintype "passive"))
      (node (ref "R8") (pin "1") (pinfunction "1_1") (pintype "passive"))
      (node (ref "R9") (pin "1") (pinfunction "1_1") (pintype "passive"))
    )
    (net (code "27") (name "Net-(D5-K)") (class "Default")
      (node (ref "D5") (pin "1") (pinfunction "K_1") (pintype "passive"))
      (node (ref "J1") (pin "3") (pinfunction "3_3") (pintype "passive"))
      (node (ref "R5") (pin "2") (pinfunction "2_2") (pintype "passive"))
      (node (ref "R8") (pin "2") (pinfunction "2_2") (pintype "passive"))
    )
    (net (code "28") (name "Net-(D6-K)") (class "Default")
      (node (ref "D6") (pin "1") (pinfunction "K_1") (pintype "passive"))
      (node (ref "J2") (pin "3") (pinfunction "3_3") (pintype "passive"))
      (node (ref "R10") (pin "2") (pinfunction "2_2") (pintype "passive"))
      (node (ref "R6") (pin "2") (pinfunction "2_2") (pintype "passive"))
    )
    (net (code "29") (name "Net-(D11-K)") (class "Default")
      (node (ref "D11") (pin "1") (pinfunction "K_1") (pintype "passive"))
      (node (ref "J3") (pin "3") (pinfunction "3_3") (pintype "passive"))
      (node (ref "R15") (pin "2") (pinfunction "2_2") (pintype "passive"))
      (node (ref "R18") (pin "2") (pinfunction "2_2") (pintype "passive"))
    )
    (net (code "30") (name "Net-(D12-K)") (class "Default")
      (node (ref "D12") (pin "1") (pinfunction "K_1") (pintype "passive"))
      (node (ref "J4") (pin "3") (pinfunction "3_3") (pintype "passive"))
      (node (ref "R16") (pin "2") (pinfunction "2_2") (pintype "passive"))
      (node (ref "R19") (pin "2") (pinfunction "2_2") (pintype "passive"))
    )
    (net (code "31") (name "Net-(D17-K)") (class "Default")
      (node (ref "D17") (pin "1") (pinfunction "K_1") (pintype "passive"))
      (node (ref "J5") (pin "3") (pinfunction "3_3") (pintype "passive"))
      (node (ref "R25") (pin "2") (pinfunction "2_2") (pintype "passive"))
      (node (ref "R29") (pin "2") (pinfunction "2_2") (pintype "passive"))
    )
    (net (code "32") (name "Net-(D18-K)") (class "Default")
      (node (ref "D18") (pin "1") (pinfunction "K_1") (pintype "passive"))
      (node (ref "J6") (pin "3") (pinfunction "3_3") (pintype "passive"))
      (node (ref "R26") (pin "2") (pinfunction "2_2") (pintype "passive"))
      (node (ref "R31") (pin "2") (pinfunction "2_2") (pintype "passive"))
    )
    (net (code "33") (name "Net-(D21-K)") (class "Default")
      (node (ref "D21") (pin "1") (pinfunction "K_1") (pintype "passive"))
      (node (ref "J7") (pin "3") (pinfunction "3_3") (pintype "passive"))
      (node (ref "R33") (pin "2") (pinfunction "2_2") (pintype "passive"))
      (node (ref "R35") (pin "2") (pinfunction "2_2") (pintype "passive"))
    )
    (net (code "34") (name "Net-(R1-Pad1)") (class "Default")
      (node (ref "R1") (pin "1") (pinfunction "1_1") (pintype "passive"))
      (node (ref "R3") (pin "2") (pinfunction "2_2") (pintype "passive"))
      (node (ref "SW1") (pin "3") (pinfunction "3_3") (pintype "passive"))
    )
    (net (code "35") (name "Net-(R2-Pad1)") (class "Default")
      (node (ref "R2") (pin "1") (pinfunction "1_1") (pintype "passive"))
      (node (ref "R4") (pin "1") (pinfunction "1_1") (pintype "passive"))
      (node (ref "SW2") (pin "3") (pinfunction "3_3") (pintype "passive"))
    )
    (net (code "36") (name "Net-(R11-Pad2)") (class "Default")
      (node (ref "R11") (pin "2") (pinfunction "2_2") (pintype "passive"))
      (node (ref "R13") (pin "2") (pinfunction "2_2") (pintype "passive"))
      (node (ref "SW3") (pin "3") (pinfunction "3_3") (pintype "passive"))
    )
    (net (code "37") (name "Net-(R12-Pad2)") (class "Default")
      (node (ref "R12") (pin "2") (pinfunction "2_2") (pintype "passive"))
      (node (ref "R14") (pin "2") (pinfunction "2_2") (pintype "passive"))
      (node (ref "SW4") (pin "3") (pinfunction "3_3") (pintype "passive"))
    )
    (net (code "38") (name "Net-(R21-Pad2)") (class "Default")
      (node (ref "R21") (pin "2") (pinfunction "2_2") (pintype "passive"))
      (node (ref "R23") (pin "1") (pinfunction "1_1") (pintype "passive"))
      (node (ref "SW5") (pin "3") (pinfunction "3_3") (pintype "passive"))
    )
    (net (code "39") (name "Net-(R22-Pad1)") (class "Default")
      (node (ref "R22") (pin "1") (pinfunction "1_1") (pintype "passive"))
      (node (ref "R24") (pin "2") (pinfunction "2_2") (pintype "passive"))
      (node (ref "SW6") (pin "3") (pinfunction "3_3") (pintype "passive"))
    )
    (net (code "40") (name "Net-(R27-Pad1)") (class "Default")
      (node (ref "R27") (pin "1") (pinfunction "1_1") (pintype "passive"))
      (node (ref "R32") (pin "1") (pinfunction "1_1") (pintype "passive"))
      (node (ref "SW7") (pin "3") (pinfunction "3_3") (pintype "passive"))
    )
    (net (code "41") (name "unconnected-(SW1-Pad1)") (class "Default")
      (node (ref "SW1") (pin "1") (pinfunction "1_1") (pintype "passive"))
    )
    (net (code "42") (name "unconnected-(SW2-Pad1)") (class "Default")
      (node (ref "SW2") (pin "1") (pinfunction "1_1") (pintype "passive"))
    )
    (net (code "43") (name "unconnected-(SW3-Pad1)") (class "Default")
      (node (ref "SW3") (pin "1") (pinfunction "1_1") (pintype "passive"))
    )
    (net (code "44") (name "unconnected-(SW4-Pad1)") (class "Default")
      (node (ref "SW4") (pin "1") (pinfunction "1_1") (pintype "passive"))
    )
    (net (code "45") (name "unconnected-(SW5-Pad1)") (class "Default")
      (node (ref "SW5") (pin "1") (pinfunction "1_1") (pintype "passive"))
    )
    (net (code "46") (name "unconnected-(SW6-Pad1)") (class "Default")
      (node (ref "SW6") (pin "1") (pinfunction "1_1") (pintype "passive"))
    )
    (net (code "47") (name "unconnected-(SW7-Pad1)") (class "Default")
      (node (ref "SW7") (pin "1") (pinfunction "1_1") (pintype "passive"))
    )
  )
)
